# McManis_BJT_H-Bridge_v006.net
KiCad netlist of a schematic drawn in EAGLE
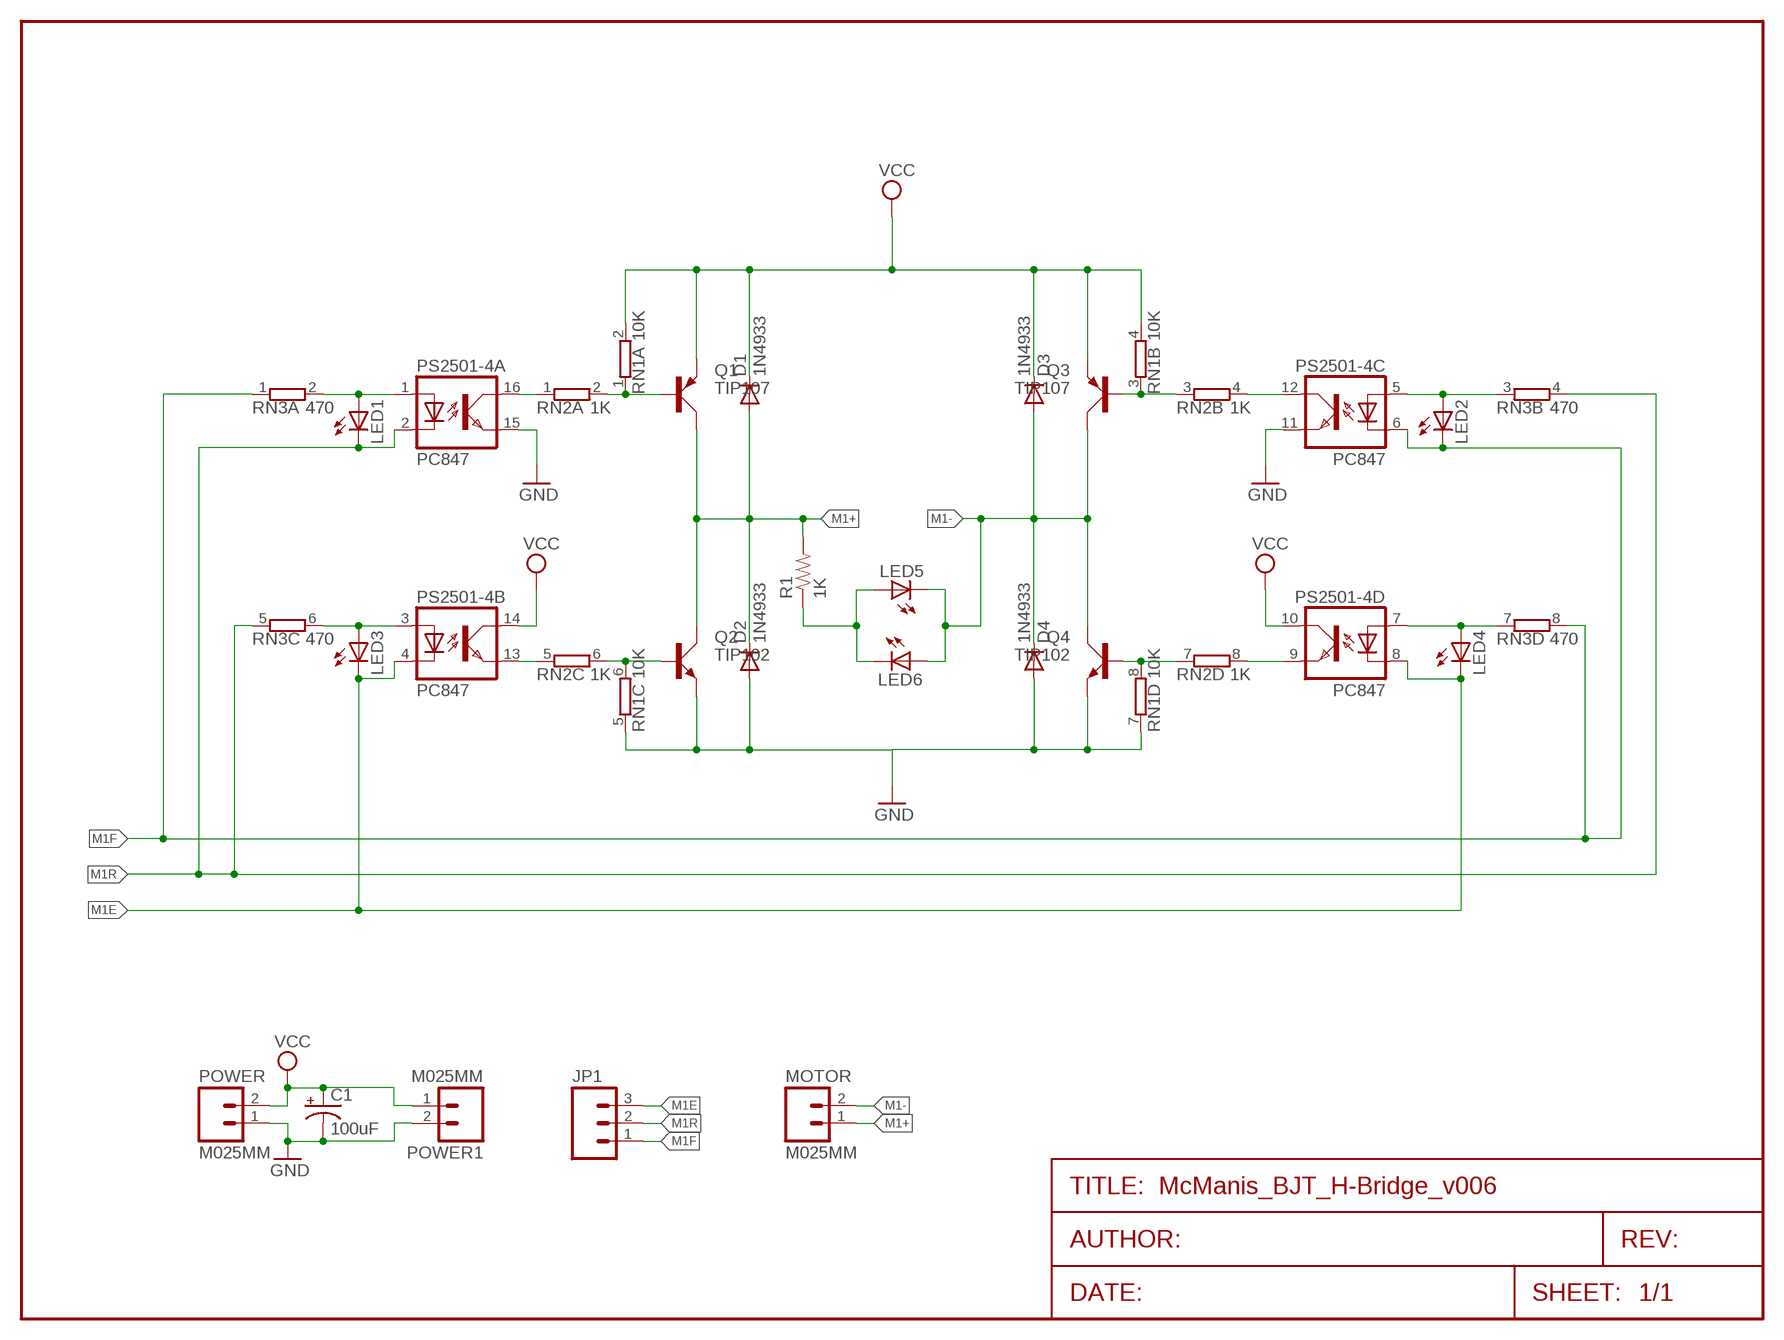
[diagram p0: schematic, sheet 1]

(export (version "E")
  (design (tool "Eeschema 10.0.6"))
  (components
    (comp (ref "C1")
      (value "100uF")
      (footprint "eagle-import:CPOL-RADIAL-100UF-25V")
      (libsource (lib "eagle-import") (part "CAP_POLPTH1"))
    )
    (comp (ref "D1")
      (value "1N4933")
      (footprint "eagle-import:DO41-10")
      (libsource (lib "eagle-import") (part "1N4933"))
    )
    (comp (ref "D2")
      (value "1N4933")
      (footprint "eagle-import:DO41-10")
      (libsource (lib "eagle-import") (part "1N4933"))
    )
    (comp (ref "D3")
      (value "1N4933")
      (footprint "eagle-import:DO41-10")
      (libsource (lib "eagle-import") (part "1N4933"))
    )
    (comp (ref "D4")
      (value "1N4933")
      (footprint "eagle-import:DO41-10")
      (libsource (lib "eagle-import") (part "1N4933"))
    )
    (comp (ref "JP1")
      (value "M03PTH")
      (footprint "eagle-import:1X03")
      (libsource (lib "eagle-import") (part "M03PTH"))
    )
    (comp (ref "LED1")
      (value "LED3MM")
      (footprint "eagle-import:LED3MM")
      (libsource (lib "eagle-import") (part "LED3MM"))
    )
    (comp (ref "LED2")
      (value "LED3MM")
      (footprint "eagle-import:LED3MM")
      (libsource (lib "eagle-import") (part "LED3MM"))
    )
    (comp (ref "LED3")
      (value "LED3MM")
      (footprint "eagle-import:LED3MM")
      (libsource (lib "eagle-import") (part "LED3MM"))
    )
    (comp (ref "LED4")
      (value "LED3MM")
      (footprint "eagle-import:LED3MM")
      (libsource (lib "eagle-import") (part "LED3MM"))
    )
    (comp (ref "LED5")
      (value "LED3MM")
      (footprint "eagle-import:LED3MM")
      (libsource (lib "eagle-import") (part "LED3MM"))
    )
    (comp (ref "LED6")
      (value "LED3MM")
      (footprint "eagle-import:LED3MM")
      (libsource (lib "eagle-import") (part "LED3MM"))
    )
    (comp (ref "MOTOR")
      (value "M025MM")
      (footprint "eagle-import:SCREWTERMINAL-5MM-2")
      (libsource (lib "eagle-import") (part "M025MM"))
    )
    (comp (ref "POWER")
      (value "M025MM")
      (footprint "eagle-import:SCREWTERMINAL-5MM-2")
      (libsource (lib "eagle-import") (part "M025MM"))
    )
    (comp (ref "POWER1")
      (value "M025MM")
      (footprint "eagle-import:SCREWTERMINAL-5MM-2")
      (libsource (lib "eagle-import") (part "M025MM"))
    )
    (comp (ref "PS2501-4")
      (value "PC847")
      (footprint "eagle-import:DIL16")
      (libsource (lib "eagle-import") (part "PC847"))
    )
    (comp (ref "Q1")
      (value "TIP107")
      (footprint "eagle-import:TO220AV")
      (libsource (lib "eagle-import") (part "TIP42C"))
    )
    (comp (ref "Q2")
      (value "TIP102")
      (footprint "eagle-import:TO220AV")
      (libsource (lib "eagle-import") (part "TIP41C"))
    )
    (comp (ref "Q3")
      (value "TIP107")
      (footprint "eagle-import:TO220AV")
      (libsource (lib "eagle-import") (part "TIP42C"))
    )
    (comp (ref "Q4")
      (value "TIP102")
      (footprint "eagle-import:TO220AV")
      (libsource (lib "eagle-import") (part "TIP41C"))
    )
    (comp (ref "R1")
      (value "1K")
      (footprint "eagle-import:AXIAL-0.4")
      (libsource (lib "eagle-import") (part "RESISTORPTH-1/4W"))
    )
    (comp (ref "RN1")
      (value "10K")
      (footprint "eagle-import:SIL8")
      (libsource (lib "eagle-import") (part "E4R"))
    )
    (comp (ref "RN2")
      (value "1K")
      (footprint "eagle-import:SIL8")
      (libsource (lib "eagle-import") (part "E4R"))
    )
    (comp (ref "RN3")
      (value "470")
      (footprint "eagle-import:SIL8")
      (libsource (lib "eagle-import") (part "E4R"))
    )
  )
  (nets
    (net (code "1") (name "GND") (class "Default")
      (node (ref "C1") (pin "2") (pinfunction "-_2") (pintype "passive"))
      (node (ref "D2") (pin "A") (pinfunction "A_A") (pintype "passive"))
      (node (ref "D4") (pin "A") (pinfunction "A_A") (pintype "passive"))
      (node (ref "POWER") (pin "1") (pinfunction "1_1") (pintype "passive"))
      (node (ref "POWER1") (pin "2") (pinfunction "2_2") (pintype "passive"))
      (node (ref "PS2501-4") (pin "11") (pinfunction "EMIT_11") (pintype "passive"))
      (node (ref "PS2501-4") (pin "15") (pinfunction "EMIT_15") (pintype "passive"))
      (node (ref "Q2") (pin "E") (pinfunction "E_E") (pintype "passive"))
      (node (ref "Q4") (pin "E") (pinfunction "E_E") (pintype "passive"))
      (node (ref "RN1") (pin "5") (pinfunction "1_5") (pintype "passive"))
      (node (ref "RN1") (pin "7") (pinfunction "1_7") (pintype "passive"))
    )
    (net (code "2") (name "M1+") (class "Default")
      (node (ref "D1") (pin "A") (pinfunction "A_A") (pintype "passive"))
      (node (ref "D2") (pin "C") (pinfunction "C_C") (pintype "passive"))
      (node (ref "MOTOR") (pin "1") (pinfunction "1_1") (pintype "passive"))
      (node (ref "Q1") (pin "C") (pinfunction "C_C") (pintype "passive"))
      (node (ref "Q2") (pin "C") (pinfunction "C_C") (pintype "passive"))
      (node (ref "R1") (pin "P$2") (pinfunction "2_P$2") (pintype "passive"))
    )
    (net (code "3") (name "M1-") (class "Default")
      (node (ref "D3") (pin "A") (pinfunction "A_A") (pintype "passive"))
      (node (ref "D4") (pin "C") (pinfunction "C_C") (pintype "passive"))
      (node (ref "LED5") (pin "K") (pinfunction "C_K") (pintype "passive"))
      (node (ref "LED6") (pin "A") (pinfunction "A_A") (pintype "passive"))
      (node (ref "MOTOR") (pin "2") (pinfunction "2_2") (pintype "passive"))
      (node (ref "Q3") (pin "C") (pinfunction "C_C") (pintype "passive"))
      (node (ref "Q4") (pin "C") (pinfunction "C_C") (pintype "passive"))
    )
    (net (code "4") (name "M1E") (class "Default")
      (node (ref "JP1") (pin "3") (pinfunction "3_3") (pintype "passive"))
      (node (ref "LED3") (pin "K") (pinfunction "C_K") (pintype "passive"))
      (node (ref "LED4") (pin "K") (pinfunction "C_K") (pintype "passive"))
      (node (ref "PS2501-4") (pin "4") (pinfunction "C_4") (pintype "passive"))
      (node (ref "PS2501-4") (pin "8") (pinfunction "C_8") (pintype "passive"))
    )
    (net (code "5") (name "M1F") (class "Default")
      (node (ref "JP1") (pin "1") (pinfunction "1_1") (pintype "passive"))
      (node (ref "LED2") (pin "K") (pinfunction "C_K") (pintype "passive"))
      (node (ref "PS2501-4") (pin "6") (pinfunction "C_6") (pintype "passive"))
      (node (ref "RN3") (pin "1") (pinfunction "1_1") (pintype "passive"))
      (node (ref "RN3") (pin "8") (pinfunction "2_8") (pintype "passive"))
    )
    (net (code "6") (name "M1R") (class "Default")
      (node (ref "JP1") (pin "2") (pinfunction "2_2") (pintype "passive"))
      (node (ref "LED1") (pin "K") (pinfunction "C_K") (pintype "passive"))
      (node (ref "PS2501-4") (pin "2") (pinfunction "C_2") (pintype "passive"))
      (node (ref "RN3") (pin "4") (pinfunction "2_4") (pintype "passive"))
      (node (ref "RN3") (pin "5") (pinfunction "1_5") (pintype "passive"))
    )
    (net (code "7") (name "Net-(LED6-C)") (class "Default")
      (node (ref "LED5") (pin "A") (pinfunction "A_A") (pintype "passive"))
      (node (ref "LED6") (pin "K") (pinfunction "C_K") (pintype "passive"))
      (node (ref "R1") (pin "P$1") (pinfunction "1_P$1") (pintype "passive"))
    )
    (net (code "8") (name "Net-(PS2501-4A-A)") (class "Default")
      (node (ref "LED1") (pin "A") (pinfunction "A_A") (pintype "passive"))
      (node (ref "PS2501-4") (pin "1") (pinfunction "A_1") (pintype "passive"))
      (node (ref "RN3") (pin "2") (pinfunction "2_2") (pintype "passive"))
    )
    (net (code "9") (name "Net-(PS2501-4A-COL)") (class "Default")
      (node (ref "PS2501-4") (pin "16") (pinfunction "COL_16") (pintype "passive"))
      (node (ref "RN2") (pin "1") (pinfunction "1_1") (pintype "passive"))
    )
    (net (code "10") (name "Net-(PS2501-4B-A)") (class "Default")
      (node (ref "LED3") (pin "A") (pinfunction "A_A") (pintype "passive"))
      (node (ref "PS2501-4") (pin "3") (pinfunction "A_3") (pintype "passive"))
      (node (ref "RN3") (pin "6") (pinfunction "2_6") (pintype "passive"))
    )
    (net (code "11") (name "Net-(PS2501-4B-EMIT)") (class "Default")
      (node (ref "PS2501-4") (pin "13") (pinfunction "EMIT_13") (pintype "passive"))
      (node (ref "RN2") (pin "5") (pinfunction "1_5") (pintype "passive"))
    )
    (net (code "12") (name "Net-(PS2501-4C-A)") (class "Default")
      (node (ref "LED2") (pin "A") (pinfunction "A_A") (pintype "passive"))
      (node (ref "PS2501-4") (pin "5") (pinfunction "A_5") (pintype "passive"))
      (node (ref "RN3") (pin "3") (pinfunction "1_3") (pintype "passive"))
    )
    (net (code "13") (name "Net-(PS2501-4C-COL)") (class "Default")
      (node (ref "PS2501-4") (pin "12") (pinfunction "COL_12") (pintype "passive"))
      (node (ref "RN2") (pin "4") (pinfunction "2_4") (pintype "passive"))
    )
    (net (code "14") (name "Net-(PS2501-4D-A)") (class "Default")
      (node (ref "LED4") (pin "A") (pinfunction "A_A") (pintype "passive"))
      (node (ref "PS2501-4") (pin "7") (pinfunction "A_7") (pintype "passive"))
      (node (ref "RN3") (pin "7") (pinfunction "1_7") (pintype "passive"))
    )
    (net (code "15") (name "Net-(PS2501-4D-EMIT)") (class "Default")
      (node (ref "PS2501-4") (pin "9") (pinfunction "EMIT_9") (pintype "passive"))
      (node (ref "RN2") (pin "8") (pinfunction "2_8") (pintype "passive"))
    )
    (net (code "16") (name "Net-(Q1-PadB)") (class "Default")
      (node (ref "Q1") (pin "B") (pinfunction "B_B") (pintype "passive"))
      (node (ref "RN1") (pin "1") (pinfunction "1_1") (pintype "passive"))
      (node (ref "RN2") (pin "2") (pinfunction "2_2") (pintype "passive"))
    )
    (net (code "17") (name "Net-(RN1B-1)") (class "Default")
      (node (ref "Q3") (pin "B") (pinfunction "B_B") (pintype "passive"))
      (node (ref "RN1") (pin "3") (pinfunction "1_3") (pintype "passive"))
      (node (ref "RN2") (pin "3") (pinfunction "1_3") (pintype "passive"))
    )
    (net (code "18") (name "Net-(RN1C-2)") (class "Default")
      (node (ref "Q2") (pin "B") (pinfunction "B_B") (pintype "passive"))
      (node (ref "RN1") (pin "6") (pinfunction "2_6") (pintype "passive"))
      (node (ref "RN2") (pin "6") (pinfunction "2_6") (pintype "passive"))
    )
    (net (code "19") (name "Net-(RN1D-2)") (class "Default")
      (node (ref "Q4") (pin "B") (pinfunction "B_B") (pintype "passive"))
      (node (ref "RN1") (pin "8") (pinfunction "2_8") (pintype "passive"))
      (node (ref "RN2") (pin "7") (pinfunction "1_7") (pintype "passive"))
    )
    (net (code "20") (name "VCC") (class "Default")
      (node (ref "C1") (pin "1") (pinfunction "+_1") (pintype "passive"))
      (node (ref "D1") (pin "C") (pinfunction "C_C") (pintype "passive"))
      (node (ref "D3") (pin "C") (pinfunction "C_C") (pintype "passive"))
      (node (ref "POWER") (pin "2") (pinfunction "2_2") (pintype "passive"))
      (node (ref "POWER1") (pin "1") (pinfunction "1_1") (pintype "passive"))
      (node (ref "PS2501-4") (pin "10") (pinfunction "COL_10") (pintype "passive"))
      (node (ref "PS2501-4") (pin "14") (pinfunction "COL_14") (pintype "passive"))
      (node (ref "Q1") (pin "E") (pinfunction "E_E") (pintype "passive"))
      (node (ref "Q3") (pin "E") (pinfunction "E_E") (pintype "passive"))
      (node (ref "RN1") (pin "2") (pinfunction "2_2") (pintype "passive"))
      (node (ref "RN1") (pin "4") (pinfunction "2_4") (pintype "passive"))
    )
  )
)
